# timerV2.net
KiCad netlist of a schematic drawn in EAGLE
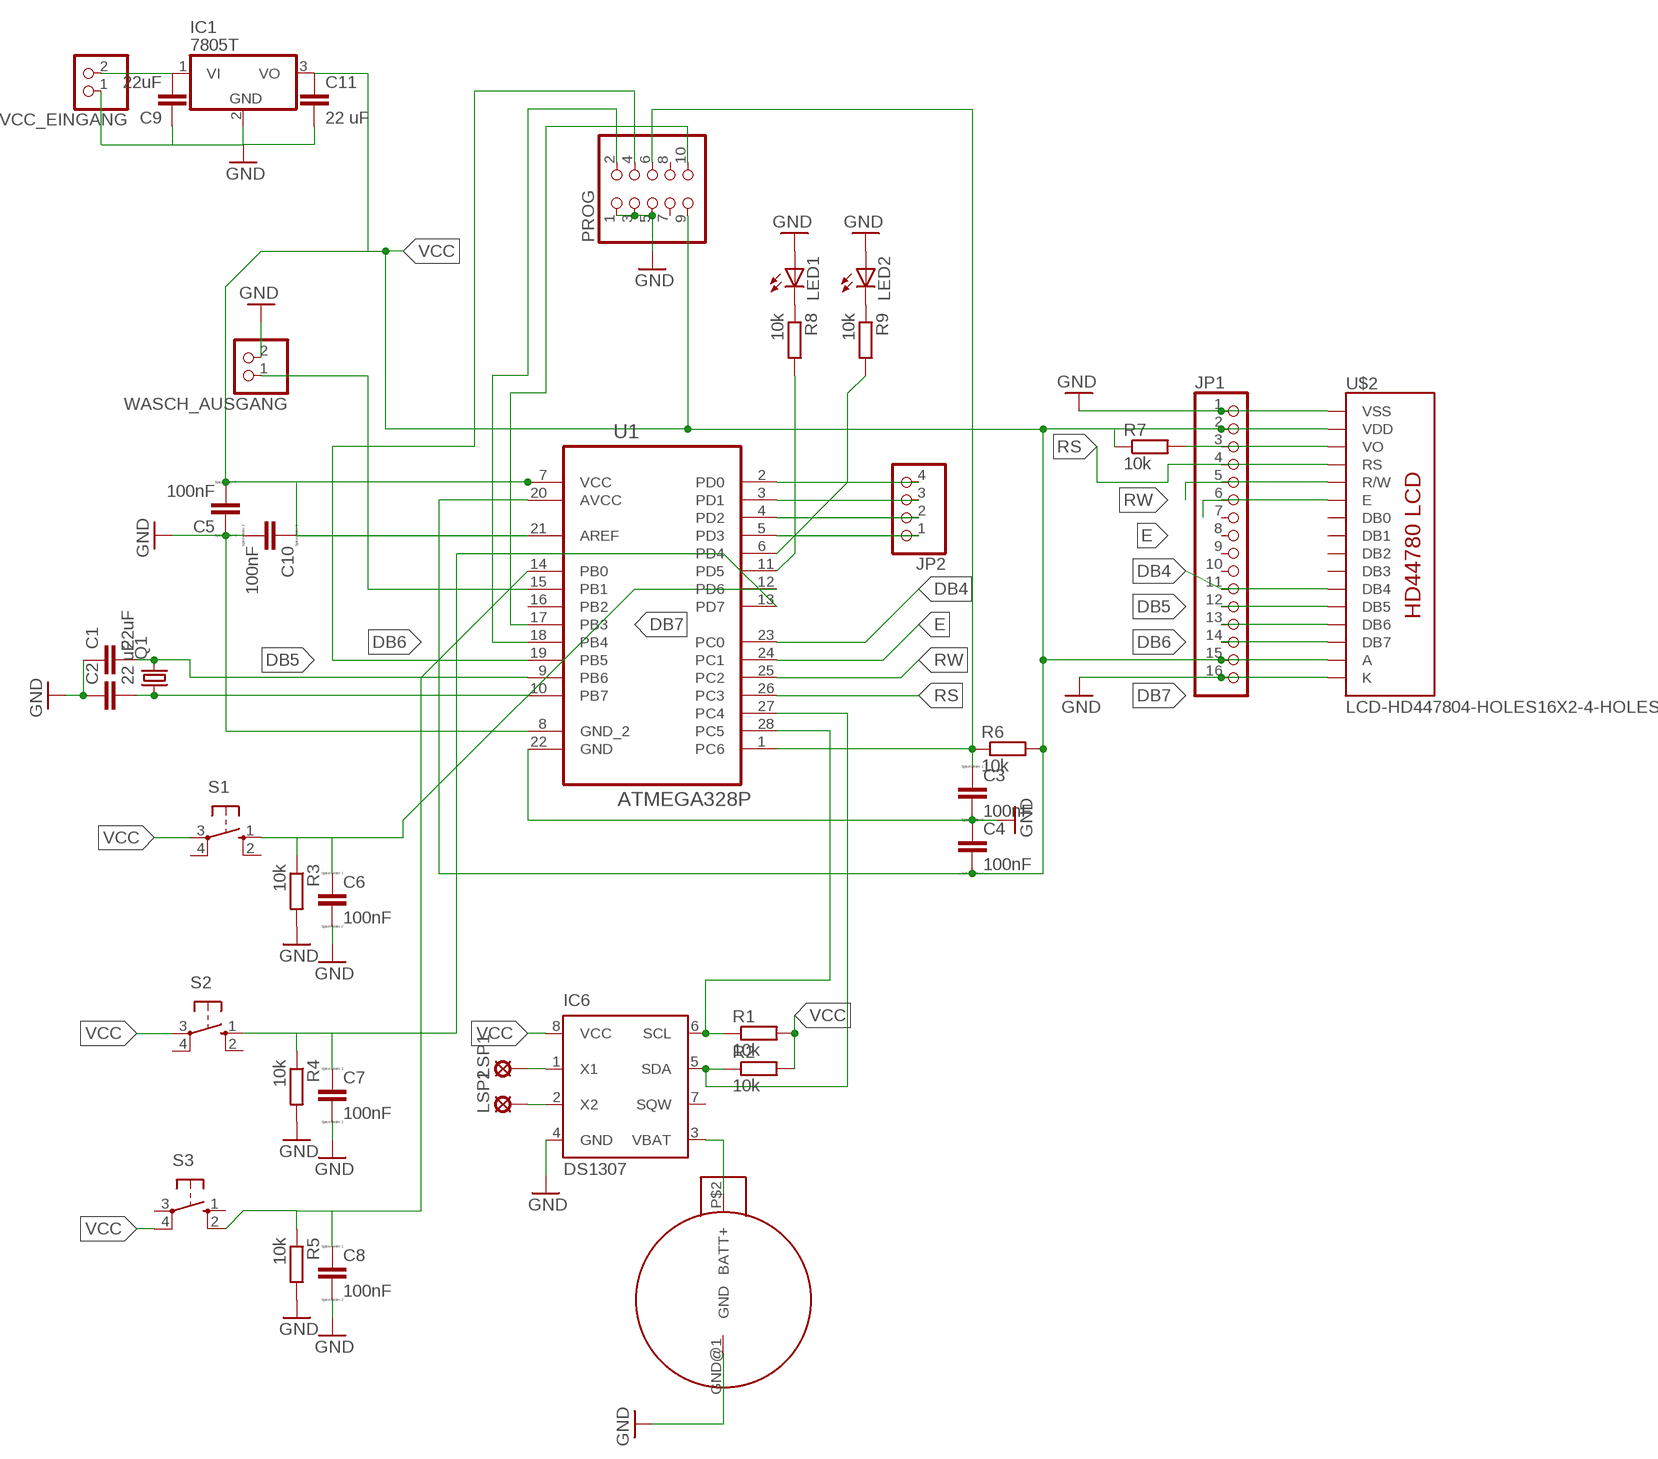
[diagram p0: schematic, sheet 1]

(export (version "E")
  (design (tool "Eeschema 10.0.6"))
  (components
    (comp (ref "C1")
      (value "22uF")
      (footprint "eagle-import:C025-025X050")
      (libsource (lib "eagle-import") (part "C-EU025-025X050"))
    )
    (comp (ref "C2")
      (value "22 uF")
      (footprint "eagle-import:C025-025X050")
      (libsource (lib "eagle-import") (part "C-EU025-025X050"))
    )
    (comp (ref "C3")
      (value "100nF")
      (footprint "eagle-import:C0603")
      (libsource (lib "eagle-import") (part "CC0603"))
    )
    (comp (ref "C4")
      (value "100nF")
      (footprint "eagle-import:C0603")
      (libsource (lib "eagle-import") (part "CC0603"))
    )
    (comp (ref "C5")
      (value "100nF")
      (footprint "eagle-import:C0603")
      (libsource (lib "eagle-import") (part "CC0603"))
    )
    (comp (ref "C6")
      (value "100nF")
      (footprint "eagle-import:C0603")
      (libsource (lib "eagle-import") (part "CC0603"))
    )
    (comp (ref "C7")
      (value "100nF")
      (footprint "eagle-import:C0603")
      (libsource (lib "eagle-import") (part "CC0603"))
    )
    (comp (ref "C8")
      (value "100nF")
      (footprint "eagle-import:C0603")
      (libsource (lib "eagle-import") (part "CC0603"))
    )
    (comp (ref "C9")
      (value "22uF")
      (footprint "eagle-import:C025-025X050")
      (libsource (lib "eagle-import") (part "C-EU025-025X050"))
    )
    (comp (ref "C10")
      (value "100nF")
      (footprint "eagle-import:C0603")
      (libsource (lib "eagle-import") (part "CC0603"))
    )
    (comp (ref "C11")
      (value "22 uF")
      (footprint "eagle-import:C025-025X050")
      (libsource (lib "eagle-import") (part "C-EU025-025X050"))
    )
    (comp (ref "IC1")
      (value "7805T")
      (footprint "eagle-import:TO220H")
      (libsource (lib "eagle-import") (part "78T05"))
    )
    (comp (ref "IC6")
      (value "DS1307")
      (footprint "eagle-import:DIL08")
      (libsource (lib "eagle-import") (part "DS1307"))
    )
    (comp (ref "JP1")
      (value "PINHD-1X16")
      (footprint "eagle-import:1X16")
      (libsource (lib "eagle-import") (part "PINHD-1X16"))
    )
    (comp (ref "JP2")
      (value "PINHD-1X4/90")
      (footprint "eagle-import:1X04_90")
      (libsource (lib "eagle-import") (part "PINHD-1X4/90"))
    )
    (comp (ref "LED1")
      (value "LED5MM")
      (footprint "eagle-import:LED5MM")
      (libsource (lib "eagle-import") (part "LED5MM"))
    )
    (comp (ref "LED2")
      (value "LED5MM")
      (footprint "eagle-import:LED5MM")
      (libsource (lib "eagle-import") (part "LED5MM"))
    )
    (comp (ref "LSP1")
      (value "LSP10")
      (footprint "eagle-import:LSP10")
      (libsource (lib "eagle-import") (part "LSP10"))
    )
    (comp (ref "LSP2")
      (value "LSP10")
      (footprint "eagle-import:LSP10")
      (libsource (lib "eagle-import") (part "LSP10"))
    )
    (comp (ref "PROG")
      (value "PINHD-2X5")
      (footprint "eagle-import:2X05")
      (libsource (lib "eagle-import") (part "PINHD-2X5"))
    )
    (comp (ref "Q1")
      (value "CRYSTALHC49U-V")
      (footprint "eagle-import:HC49U-V")
      (libsource (lib "eagle-import") (part "CRYSTALHC49U-V"))
    )
    (comp (ref "R1")
      (value "10k")
      (footprint "eagle-import:0204_7")
      (libsource (lib "eagle-import") (part "R-EU_0204/7"))
    )
    (comp (ref "R2")
      (value "10k")
      (footprint "eagle-import:0204_7")
      (libsource (lib "eagle-import") (part "R-EU_0204/7"))
    )
    (comp (ref "R3")
      (value "10k")
      (footprint "eagle-import:0204_7")
      (libsource (lib "eagle-import") (part "R-EU_0204/7"))
    )
    (comp (ref "R4")
      (value "10k")
      (footprint "eagle-import:0204_7")
      (libsource (lib "eagle-import") (part "R-EU_0204/7"))
    )
    (comp (ref "R5")
      (value "10k")
      (footprint "eagle-import:0204_7")
      (libsource (lib "eagle-import") (part "R-EU_0204/7"))
    )
    (comp (ref "R6")
      (value "10k")
      (footprint "eagle-import:0204_7")
      (libsource (lib "eagle-import") (part "R-EU_0204/7"))
    )
    (comp (ref "R7")
      (value "10k")
      (footprint "eagle-import:0204_7")
      (libsource (lib "eagle-import") (part "R-EU_0204/7"))
    )
    (comp (ref "R8")
      (value "10k")
      (footprint "eagle-import:0204_7")
      (libsource (lib "eagle-import") (part "R-EU_0204/7"))
    )
    (comp (ref "R9")
      (value "10k")
      (footprint "eagle-import:0204_7")
      (libsource (lib "eagle-import") (part "R-EU_0204/7"))
    )
    (comp (ref "S1")
      (value "10-XX")
      (footprint "eagle-import:B3F-10XX")
      (fields (field (name "MPN") "B3F-1000"))
      (libsource (lib "eagle-import") (part "10-XX"))
    )
    (comp (ref "S2")
      (value "10-XX")
      (footprint "eagle-import:B3F-10XX")
      (fields (field (name "MPN") "B3F-1000"))
      (libsource (lib "eagle-import") (part "10-XX"))
    )
    (comp (ref "S3")
      (value "10-XX")
      (footprint "eagle-import:B3F-10XX")
      (fields (field (name "MPN") "B3F-1000"))
      (libsource (lib "eagle-import") (part "10-XX"))
    )
    (comp (ref "U$1")
      (value "CR2032")
      (footprint "eagle-import:CR2023")
      (libsource (lib "eagle-import") (part "CR2032"))
    )
    (comp (ref "U$2")
      (value "LCD-HD447804-HOLES16X2-4-HOLES")
      (footprint "eagle-import:LCD-16X2-4HOLES")
      (libsource (lib "eagle-import") (part "LCD-HD4478016X2-4-HOLES4-HOLES"))
    )
    (comp (ref "U1")
      (value "ATMEGA328P")
      (footprint "eagle-import:DIP254P762X457-28")
      (fields (field (name "MPN") "ATMEGA328P-PU"))
      (libsource (lib "eagle-import") (part "ATMEGA328P-PU"))
    )
    (comp (ref "VCC_EINGANG")
      (value "PINHD-1X2")
      (footprint "eagle-import:1X02")
      (libsource (lib "eagle-import") (part "PINHD-1X2"))
    )
    (comp (ref "WASCH_AUSGANG")
      (value "PINHD-1X2")
      (footprint "eagle-import:1X02")
      (libsource (lib "eagle-import") (part "PINHD-1X2"))
    )
  )
  (nets
    (net (code "1") (name "DB4") (class "Default")
      (node (ref "JP1") (pin "11") (pinfunction "11_11") (pintype "passive"))
      (node (ref "U$2") (pin "11") (pinfunction "DB4_11") (pintype "bidirectional"))
      (node (ref "U1") (pin "23") (pinfunction "PC0_23") (pintype "bidirectional"))
    )
    (net (code "2") (name "DB5") (class "Default")
      (node (ref "JP1") (pin "12") (pinfunction "12_12") (pintype "passive"))
      (node (ref "PROG") (pin "4") (pinfunction "4_4") (pintype "passive"))
      (node (ref "U$2") (pin "12") (pinfunction "DB5_12") (pintype "bidirectional"))
      (node (ref "U1") (pin "19") (pinfunction "PB5_19") (pintype "bidirectional"))
    )
    (net (code "3") (name "DB6") (class "Default")
      (node (ref "JP1") (pin "13") (pinfunction "13_13") (pintype "passive"))
      (node (ref "PROG") (pin "2") (pinfunction "2_2") (pintype "passive"))
      (node (ref "U$2") (pin "13") (pinfunction "DB6_13") (pintype "bidirectional"))
      (node (ref "U1") (pin "18") (pinfunction "PB4_18") (pintype "bidirectional"))
    )
    (net (code "4") (name "DB7") (class "Default")
      (node (ref "JP1") (pin "14") (pinfunction "14_14") (pintype "passive"))
      (node (ref "PROG") (pin "10") (pinfunction "10_10") (pintype "passive"))
      (node (ref "U$2") (pin "14") (pinfunction "DB7_14") (pintype "bidirectional"))
      (node (ref "U1") (pin "17") (pinfunction "PB3_17") (pintype "bidirectional"))
    )
    (net (code "5") (name "E") (class "Default")
      (node (ref "JP1") (pin "6") (pinfunction "6_6") (pintype "passive"))
      (node (ref "U$2") (pin "6") (pinfunction "E_6") (pintype "input"))
      (node (ref "U1") (pin "24") (pinfunction "PC1_24") (pintype "bidirectional"))
    )
    (net (code "6") (name "GND") (class "Default")
      (node (ref "C1") (pin "1") (pinfunction "1_1") (pintype "passive"))
      (node (ref "C10") (pin "2") (pinfunction "2_2") (pintype "passive"))
      (node (ref "C11") (pin "2") (pinfunction "2_2") (pintype "passive"))
      (node (ref "C2") (pin "1") (pinfunction "1_1") (pintype "passive"))
      (node (ref "C3") (pin "2") (pinfunction "2_2") (pintype "passive"))
      (node (ref "C4") (pin "1") (pinfunction "1_1") (pintype "passive"))
      (node (ref "C5") (pin "1") (pinfunction "1_1") (pintype "passive"))
      (node (ref "C6") (pin "2") (pinfunction "2_2") (pintype "passive"))
      (node (ref "C7") (pin "2") (pinfunction "2_2") (pintype "passive"))
      (node (ref "C8") (pin "2") (pinfunction "2_2") (pintype "passive"))
      (node (ref "C9") (pin "1") (pinfunction "1_1") (pintype "passive"))
      (node (ref "IC1") (pin "2") (pinfunction "GND_2") (pintype "passive"))
      (node (ref "IC6") (pin "4") (pinfunction "GND_4") (pintype "power_in"))
      (node (ref "JP1") (pin "1") (pinfunction "1_1") (pintype "passive"))
      (node (ref "JP1") (pin "16") (pinfunction "16_16") (pintype "passive"))
      (node (ref "LED1") (pin "A") (pinfunction "A_A") (pintype "passive"))
      (node (ref "LED2") (pin "A") (pinfunction "A_A") (pintype "passive"))
      (node (ref "PROG") (pin "1") (pinfunction "1_1") (pintype "passive"))
      (node (ref "PROG") (pin "3") (pinfunction "3_3") (pintype "passive"))
      (node (ref "PROG") (pin "5") (pinfunction "5_5") (pintype "passive"))
      (node (ref "R3") (pin "2") (pinfunction "2_2") (pintype "passive"))
      (node (ref "R4") (pin "2") (pinfunction "2_2") (pintype "passive"))
      (node (ref "R5") (pin "2") (pinfunction "2_2") (pintype "passive"))
      (node (ref "U$1") (pin "GND@1") (pinfunction "GND_GND@1") (pintype "power_in"))
      (node (ref "U$2") (pin "1") (pinfunction "VSS_1") (pintype "power_in"))
      (node (ref "U$2") (pin "16") (pinfunction "K_16") (pintype "power_in"))
      (node (ref "U1") (pin "22") (pinfunction "GND_22") (pintype "passive"))
      (node (ref "U1") (pin "8") (pinfunction "GND_2_8") (pintype "passive"))
      (node (ref "VCC_EINGANG") (pin "1") (pinfunction "1_1") (pintype "passive"))
      (node (ref "WASCH_AUSGANG") (pin "2") (pinfunction "2_2") (pintype "passive"))
    )
    (net (code "7") (name "Net-(IC1-VI)") (class "Default")
      (node (ref "C9") (pin "2") (pinfunction "2_2") (pintype "passive"))
      (node (ref "IC1") (pin "1") (pinfunction "VI_1") (pintype "input"))
      (node (ref "VCC_EINGANG") (pin "2") (pinfunction "2_2") (pintype "passive"))
    )
    (net (code "8") (name "Net-(IC6-SCL)") (class "Default")
      (node (ref "IC6") (pin "6") (pinfunction "SCL_6") (pintype "input"))
      (node (ref "R1") (pin "1") (pinfunction "1_1") (pintype "passive"))
      (node (ref "U1") (pin "28") (pinfunction "PC5_28") (pintype "bidirectional"))
    )
    (net (code "9") (name "Net-(IC6-SDA)") (class "Default")
      (node (ref "IC6") (pin "5") (pinfunction "SDA_5") (pintype "bidirectional"))
      (node (ref "R2") (pin "1") (pinfunction "1_1") (pintype "passive"))
      (node (ref "U1") (pin "27") (pinfunction "PC4_27") (pintype "bidirectional"))
    )
    (net (code "10") (name "Net-(IC6-VBAT)") (class "Default")
      (node (ref "IC6") (pin "3") (pinfunction "VBAT_3") (pintype "passive"))
      (node (ref "U$1") (pin "P$2") (pinfunction "BATT+_P$2") (pintype "output"))
    )
    (net (code "11") (name "Net-(IC6-X1)") (class "Default")
      (node (ref "IC6") (pin "1") (pinfunction "X1_1") (pintype "input"))
      (node (ref "LSP1") (pin "MP") (pinfunction "MP_MP") (pintype "passive"))
    )
    (net (code "12") (name "Net-(IC6-X2)") (class "Default")
      (node (ref "IC6") (pin "2") (pinfunction "X2_2") (pintype "output"))
      (node (ref "LSP2") (pin "MP") (pinfunction "MP_MP") (pintype "passive"))
    )
    (net (code "13") (name "Net-(LED1-C)") (class "Default")
      (node (ref "LED1") (pin "K") (pinfunction "C_K") (pintype "passive"))
      (node (ref "R8") (pin "1") (pinfunction "1_1") (pintype "passive"))
    )
    (net (code "14") (name "Net-(LED2-C)") (class "Default")
      (node (ref "LED2") (pin "K") (pinfunction "C_K") (pintype "passive"))
      (node (ref "R9") (pin "1") (pinfunction "1_1") (pintype "passive"))
    )
    (net (code "15") (name "Net-(S1-S)") (class "Default")
      (node (ref "C6") (pin "1") (pinfunction "1_1") (pintype "passive"))
      (node (ref "R3") (pin "1") (pinfunction "1_1") (pintype "passive"))
      (node (ref "S1") (pin "1") (pinfunction "S_1") (pintype "passive"))
      (node (ref "U1") (pin "12") (pinfunction "PD6_12") (pintype "bidirectional"))
    )
    (net (code "16") (name "Net-(S2-S)") (class "Default")
      (node (ref "C7") (pin "1") (pinfunction "1_1") (pintype "passive"))
      (node (ref "R4") (pin "1") (pinfunction "1_1") (pintype "passive"))
      (node (ref "S2") (pin "1") (pinfunction "S_1") (pintype "passive"))
      (node (ref "U1") (pin "13") (pinfunction "PD7_13") (pintype "bidirectional"))
    )
    (net (code "17") (name "Net-(S3-S1)") (class "Default")
      (node (ref "C8") (pin "1") (pinfunction "1_1") (pintype "passive"))
      (node (ref "R5") (pin "1") (pinfunction "1_1") (pintype "passive"))
      (node (ref "S3") (pin "2") (pinfunction "S1_2") (pintype "passive"))
      (node (ref "U1") (pin "14") (pinfunction "PB0_14") (pintype "bidirectional"))
    )
    (net (code "18") (name "Net-(U$2-VO)") (class "Default")
      (node (ref "JP1") (pin "3") (pinfunction "3_3") (pintype "passive"))
      (node (ref "R7") (pin "2") (pinfunction "2_2") (pintype "passive"))
      (node (ref "U$2") (pin "3") (pinfunction "VO_3") (pintype "bidirectional"))
    )
    (net (code "19") (name "Net-(U1-PB1)") (class "Default")
      (node (ref "U1") (pin "15") (pinfunction "PB1_15") (pintype "bidirectional"))
      (node (ref "WASCH_AUSGANG") (pin "1") (pinfunction "1_1") (pintype "passive"))
    )
    (net (code "20") (name "Net-(U1-PB6)") (class "Default")
      (node (ref "C1") (pin "2") (pinfunction "2_2") (pintype "passive"))
      (node (ref "Q1") (pin "2") (pinfunction "2_2") (pintype "passive"))
      (node (ref "U1") (pin "9") (pinfunction "PB6_9") (pintype "bidirectional"))
    )
    (net (code "21") (name "Net-(U1-PB7)") (class "Default")
      (node (ref "C2") (pin "2") (pinfunction "2_2") (pintype "passive"))
      (node (ref "Q1") (pin "1") (pinfunction "1_1") (pintype "passive"))
      (node (ref "U1") (pin "10") (pinfunction "PB7_10") (pintype "bidirectional"))
    )
    (net (code "22") (name "Net-(U1-PC6)") (class "Default")
      (node (ref "C3") (pin "1") (pinfunction "1_1") (pintype "passive"))
      (node (ref "PROG") (pin "6") (pinfunction "6_6") (pintype "passive"))
      (node (ref "R6") (pin "1") (pinfunction "1_1") (pintype "passive"))
      (node (ref "U1") (pin "1") (pinfunction "PC6_1") (pintype "bidirectional"))
    )
    (net (code "23") (name "Net-(U1-PD0)") (class "Default")
      (node (ref "JP2") (pin "4") (pinfunction "4_4") (pintype "passive"))
      (node (ref "U1") (pin "2") (pinfunction "PD0_2") (pintype "bidirectional"))
    )
    (net (code "24") (name "Net-(U1-PD1)") (class "Default")
      (node (ref "JP2") (pin "3") (pinfunction "3_3") (pintype "passive"))
      (node (ref "U1") (pin "3") (pinfunction "PD1_3") (pintype "bidirectional"))
    )
    (net (code "25") (name "Net-(U1-PD2)") (class "Default")
      (node (ref "JP2") (pin "2") (pinfunction "2_2") (pintype "passive"))
      (node (ref "U1") (pin "4") (pinfunction "PD2_4") (pintype "bidirectional"))
    )
    (net (code "26") (name "Net-(U1-PD3)") (class "Default")
      (node (ref "JP2") (pin "1") (pinfunction "1_1") (pintype "passive"))
      (node (ref "U1") (pin "5") (pinfunction "PD3_5") (pintype "bidirectional"))
    )
    (net (code "27") (name "Net-(U1-PD4)") (class "Default")
      (node (ref "R9") (pin "2") (pinfunction "2_2") (pintype "passive"))
      (node (ref "U1") (pin "6") (pinfunction "PD4_6") (pintype "bidirectional"))
    )
    (net (code "28") (name "Net-(U1-PD5)") (class "Default")
      (node (ref "R8") (pin "2") (pinfunction "2_2") (pintype "passive"))
      (node (ref "U1") (pin "11") (pinfunction "PD5_11") (pintype "bidirectional"))
    )
    (net (code "29") (name "RS") (class "Default")
      (node (ref "JP1") (pin "4") (pinfunction "4_4") (pintype "passive"))
      (node (ref "U$2") (pin "4") (pinfunction "RS_4") (pintype "input"))
      (node (ref "U1") (pin "26") (pinfunction "PC3_26") (pintype "bidirectional"))
    )
    (net (code "30") (name "RW") (class "Default")
      (node (ref "JP1") (pin "5") (pinfunction "5_5") (pintype "passive"))
      (node (ref "U$2") (pin "5") (pinfunction "R/W_5") (pintype "input"))
      (node (ref "U1") (pin "25") (pinfunction "PC2_25") (pintype "bidirectional"))
    )
    (net (code "31") (name "VCC") (class "Default")
      (node (ref "C10") (pin "1") (pinfunction "1_1") (pintype "passive"))
      (node (ref "C11") (pin "1") (pinfunction "1_1") (pintype "passive"))
      (node (ref "C4") (pin "2") (pinfunction "2_2") (pintype "passive"))
      (node (ref "C5") (pin "2") (pinfunction "2_2") (pintype "passive"))
      (node (ref "IC1") (pin "3") (pinfunction "VO_3") (pintype "passive"))
      (node (ref "IC6") (pin "8") (pinfunction "VCC_8") (pintype "power_in"))
      (node (ref "JP1") (pin "15") (pinfunction "15_15") (pintype "passive"))
      (node (ref "JP1") (pin "2") (pinfunction "2_2") (pintype "passive"))
      (node (ref "PROG") (pin "9") (pinfunction "9_9") (pintype "passive"))
      (node (ref "R1") (pin "2") (pinfunction "2_2") (pintype "passive"))
      (node (ref "R2") (pin "2") (pinfunction "2_2") (pintype "passive"))
      (node (ref "R6") (pin "2") (pinfunction "2_2") (pintype "passive"))
      (node (ref "R7") (pin "1") (pinfunction "1_1") (pintype "passive"))
      (node (ref "S1") (pin "3") (pinfunction "P_3") (pintype "passive"))
      (node (ref "S2") (pin "3") (pinfunction "P_3") (pintype "passive"))
      (node (ref "S3") (pin "4") (pinfunction "P1_4") (pintype "passive"))
      (node (ref "U$2") (pin "15") (pinfunction "A_15") (pintype "power_in"))
      (node (ref "U$2") (pin "2") (pinfunction "VDD_2") (pintype "power_in"))
      (node (ref "U1") (pin "20") (pinfunction "AVCC_20") (pintype "power_in"))
      (node (ref "U1") (pin "21") (pinfunction "AREF_21") (pintype "input"))
      (node (ref "U1") (pin "7") (pinfunction "VCC_7") (pintype "power_in"))
    )
    (net (code "32") (name "unconnected-(IC6-SQW-Pad7)") (class "Default")
      (node (ref "IC6") (pin "7") (pinfunction "SQW_7") (pintype "open_collector"))
    )
    (net (code "33") (name "unconnected-(JP1-Pad7)") (class "Default")
      (node (ref "JP1") (pin "7") (pinfunction "7_7") (pintype "passive"))
    )
    (net (code "34") (name "unconnected-(JP1-Pad8)") (class "Default")
      (node (ref "JP1") (pin "8") (pinfunction "8_8") (pintype "passive"))
    )
    (net (code "35") (name "unconnected-(JP1-Pad9)") (class "Default")
      (node (ref "JP1") (pin "9") (pinfunction "9_9") (pintype "passive"))
    )
    (net (code "36") (name "unconnected-(JP1-Pad10)") (class "Default")
      (node (ref "JP1") (pin "10") (pinfunction "10_10") (pintype "passive"))
    )
    (net (code "37") (name "unconnected-(PROG-Pad7)") (class "Default")
      (node (ref "PROG") (pin "7") (pinfunction "7_7") (pintype "passive"))
    )
    (net (code "38") (name "unconnected-(PROG-Pad8)") (class "Default")
      (node (ref "PROG") (pin "8") (pinfunction "8_8") (pintype "passive"))
    )
    (net (code "39") (name "unconnected-(S1-P1-Pad4)") (class "Default")
      (node (ref "S1") (pin "4") (pinfunction "P1_4") (pintype "passive"))
    )
    (net (code "40") (name "unconnected-(S1-S1-Pad2)") (class "Default")
      (node (ref "S1") (pin "2") (pinfunction "S1_2") (pintype "passive"))
    )
    (net (code "41") (name "unconnected-(S2-P1-Pad4)") (class "Default")
      (node (ref "S2") (pin "4") (pinfunction "P1_4") (pintype "passive"))
    )
    (net (code "42") (name "unconnected-(S2-S1-Pad2)") (class "Default")
      (node (ref "S2") (pin "2") (pinfunction "S1_2") (pintype "passive"))
    )
    (net (code "43") (name "unconnected-(S3-P-Pad3)") (class "Default")
      (node (ref "S3") (pin "3") (pinfunction "P_3") (pintype "passive"))
    )
    (net (code "44") (name "unconnected-(S3-S-Pad1)") (class "Default")
      (node (ref "S3") (pin "1") (pinfunction "S_1") (pintype "passive"))
    )
    (net (code "45") (name "unconnected-(U$2-DB0-Pad7)") (class "Default")
      (node (ref "U$2") (pin "7") (pinfunction "DB0_7") (pintype "bidirectional"))
    )
    (net (code "46") (name "unconnected-(U$2-DB1-Pad8)") (class "Default")
      (node (ref "U$2") (pin "8") (pinfunction "DB1_8") (pintype "bidirectional"))
    )
    (net (code "47") (name "unconnected-(U$2-DB2-Pad9)") (class "Default")
      (node (ref "U$2") (pin "9") (pinfunction "DB2_9") (pintype "bidirectional"))
    )
    (net (code "48") (name "unconnected-(U$2-DB3-Pad10)") (class "Default")
      (node (ref "U$2") (pin "10") (pinfunction "DB3_10") (pintype "bidirectional"))
    )
    (net (code "49") (name "unconnected-(U1-PB2-Pad16)") (class "Default")
      (node (ref "U1") (pin "16") (pinfunction "PB2_16") (pintype "bidirectional"))
    )
  )
)
